# Power.net
KiCad netlist of a schematic drawn in Altium Designer
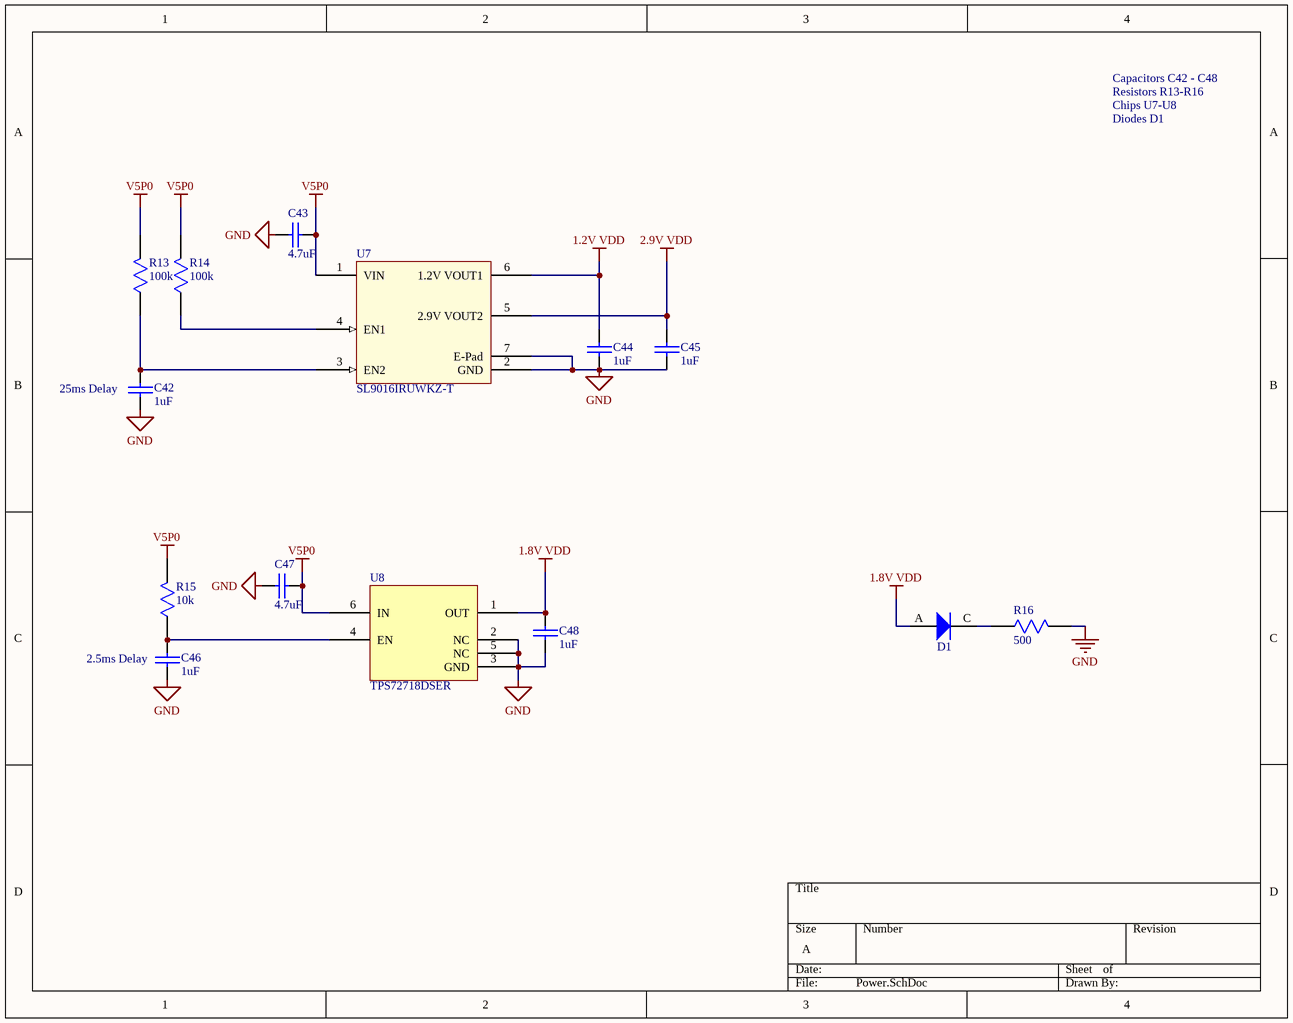
[diagram p0: Power.SchDoc]

(export (version "E")
  (design (tool "Eeschema 10.0.6"))
  (components
    (comp (ref "C42")
      (value "1uF")
      (footprint "SMD CAP 0402")
      (libsource (lib "DA_Component_Library") (part "Capacitor"))
    )
    (comp (ref "C43")
      (value "4.7uF")
      (footprint "SMD CAP 0402")
      (libsource (lib "DA_Component_Library") (part "Capacitor"))
    )
    (comp (ref "C44")
      (value "1uF")
      (footprint "SMD CAP 0402")
      (libsource (lib "DA_Component_Library") (part "Capacitor"))
    )
    (comp (ref "C45")
      (value "1uF")
      (footprint "SMD CAP 0402")
      (libsource (lib "DA_Component_Library") (part "Capacitor"))
    )
    (comp (ref "C46")
      (value "1uF")
      (footprint "SMD CAP 0402")
      (libsource (lib "DA_Component_Library") (part "Capacitor"))
    )
    (comp (ref "C47")
      (value "4.7uF")
      (footprint "SMD CAP 0402")
      (libsource (lib "DA_Component_Library") (part "Capacitor"))
    )
    (comp (ref "C48")
      (value "1uF")
      (footprint "SMD CAP 0402")
      (libsource (lib "DA_Component_Library") (part "Capacitor"))
    )
    (comp (ref "D1")
      (value "LED 0603")
      (footprint "LED_0603")
      (description "LTST_C195TBJRKT")
      (libsource (lib "DA_Component_Library") (part "LED 0603"))
    )
    (comp (ref "R13")
      (value "100k")
      (footprint "SMD RES 0402")
      (libsource (lib "DA_Component_Library") (part "Resistor"))
    )
    (comp (ref "R14")
      (value "100k")
      (footprint "SMD RES 0402")
      (libsource (lib "DA_Component_Library") (part "Resistor"))
    )
    (comp (ref "R15")
      (value "10k")
      (footprint "SMD RES 0402")
      (libsource (lib "DA_Component_Library") (part "Resistor"))
    )
    (comp (ref "R16")
      (value "500")
      (footprint "SMD RES 0402")
      (libsource (lib "DA_Component_Library") (part "Resistor"))
    )
    (comp (ref "U7")
      (value "SL9016IRUWKZ-T")
      (footprint "UTDFN")
      (libsource (lib "Miniscope") (part "SL9016IRUWKZ-T"))
    )
    (comp (ref "U8")
      (value "TPS72718DSER")
      (footprint "DSE")
      (description "Single 1.8V Linear Regulator")
      (libsource (lib "Miniscope") (part "TPS72718DSER"))
    )
  )
  (nets
    (net (code "1") (name "1.2V VDD") (class "Default")
      (node (ref "C44") (pin "0") (pinfunction "0_0") (pintype "passive"))
      (node (ref "U7") (pin "6") (pinfunction "1.2V_VOUT1_6") (pintype "power_in"))
    )
    (net (code "2") (name "1.8V VDD") (class "Default")
      (node (ref "C48") (pin "1") (pinfunction "1_1") (pintype "passive"))
      (node (ref "D1") (pin "A") (pinfunction "A_A") (pintype "passive"))
      (node (ref "U8") (pin "1") (pinfunction "OUT_1") (pintype "power_in"))
    )
    (net (code "3") (name "2.9V VDD") (class "Default")
      (node (ref "C45") (pin "0") (pinfunction "0_0") (pintype "passive"))
      (node (ref "U7") (pin "5") (pinfunction "2.9V_VOUT2_5") (pintype "power_in"))
    )
    (net (code "4") (name "GND") (class "Default")
      (node (ref "C42") (pin "1") (pinfunction "1_1") (pintype "passive"))
      (node (ref "C43") (pin "1") (pinfunction "1_1") (pintype "passive"))
      (node (ref "C44") (pin "1") (pinfunction "1_1") (pintype "passive"))
      (node (ref "C45") (pin "1") (pinfunction "1_1") (pintype "passive"))
      (node (ref "C46") (pin "1") (pinfunction "1_1") (pintype "passive"))
      (node (ref "C47") (pin "0") (pinfunction "0_0") (pintype "passive"))
      (node (ref "C48") (pin "0") (pinfunction "0_0") (pintype "passive"))
      (node (ref "R16") (pin "1") (pinfunction "1_1") (pintype "passive"))
      (node (ref "U7") (pin "2") (pinfunction "GND_2") (pintype "power_in"))
      (node (ref "U7") (pin "7") (pinfunction "E-Pad_7") (pintype "power_in"))
      (node (ref "U8") (pin "2") (pinfunction "NC_2") (pintype "passive"))
      (node (ref "U8") (pin "3") (pinfunction "GND_3") (pintype "power_in"))
      (node (ref "U8") (pin "5") (pinfunction "NC_5") (pintype "power_in"))
    )
    (net (code "5") (name "Net-(D1-PadC)") (class "Default")
      (node (ref "D1") (pin "C") (pinfunction "C_C") (pintype "passive"))
      (node (ref "R16") (pin "0") (pinfunction "0_0") (pintype "passive"))
    )
    (net (code "6") (name "Net-(U7-EN1)") (class "Default")
      (node (ref "R14") (pin "0") (pinfunction "0_0") (pintype "passive"))
      (node (ref "U7") (pin "4") (pinfunction "EN1_4") (pintype "input"))
    )
    (net (code "7") (name "Net-(U7-EN2)") (class "Default")
      (node (ref "C42") (pin "0") (pinfunction "0_0") (pintype "passive"))
      (node (ref "R13") (pin "0") (pinfunction "0_0") (pintype "passive"))
      (node (ref "U7") (pin "3") (pinfunction "EN2_3") (pintype "input"))
    )
    (net (code "8") (name "Net-(U8-EN)") (class "Default")
      (node (ref "C46") (pin "0") (pinfunction "0_0") (pintype "passive"))
      (node (ref "R15") (pin "0") (pinfunction "0_0") (pintype "passive"))
      (node (ref "U8") (pin "4") (pinfunction "EN_4") (pintype "power_in"))
    )
    (net (code "9") (name "V5P0") (class "Default")
      (node (ref "C43") (pin "0") (pinfunction "0_0") (pintype "passive"))
      (node (ref "C47") (pin "1") (pinfunction "1_1") (pintype "passive"))
      (node (ref "R13") (pin "1") (pinfunction "1_1") (pintype "passive"))
      (node (ref "R14") (pin "1") (pinfunction "1_1") (pintype "passive"))
      (node (ref "R15") (pin "1") (pinfunction "1_1") (pintype "passive"))
      (node (ref "U7") (pin "1") (pinfunction "VIN_1") (pintype "power_in"))
      (node (ref "U8") (pin "6") (pinfunction "IN_6") (pintype "power_in"))
    )
  )
)
